# POWER.net
KiCad netlist of a schematic drawn in Altium Designer
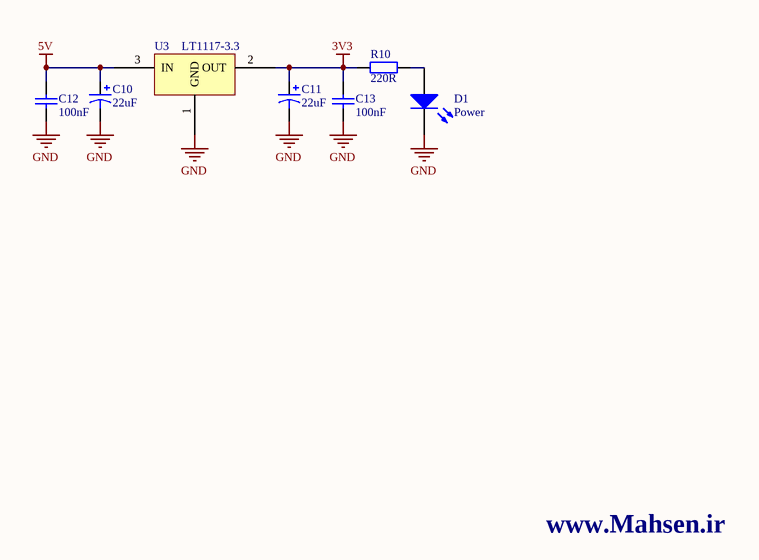
[diagram p0: POWER.SchDoc]

(export (version "E")
  (design (tool "Eeschema 10.0.6"))
  (components
    (comp (ref "C10")
      (value "22uF")
      (footprint "CAPR5-4X5")
      (description "Polarized Capacitor (Surface Mount)")
      (fields (field (name "PUBLISHER") "Altium Limited"))
      (libsource (lib "Miscellaneous Devices") (part "Cap Pol3"))
    )
    (comp (ref "C11")
      (value "22uF")
      (footprint "CAPR5-4X5")
      (description "Polarized Capacitor (Surface Mount)")
      (fields (field (name "PUBLISHER") "Altium Limited"))
      (libsource (lib "Miscellaneous Devices") (part "Cap Pol3"))
    )
    (comp (ref "C12")
      (value "100nF")
      (footprint "0805")
      (description "Capacitor")
      (fields (field (name "PUBLISHER") "Altium Limited"))
      (libsource (lib "Miscellaneous Devices") (part "Cap"))
    )
    (comp (ref "C13")
      (value "100nF")
      (footprint "0805")
      (description "Capacitor")
      (fields (field (name "PUBLISHER") "Altium Limited"))
      (libsource (lib "Miscellaneous Devices") (part "Cap"))
    )
    (comp (ref "D1")
      (value "Power")
      (footprint "3.5X2.8X1.9")
      (description "Typical BLUE SiC LED")
      (fields (field (name "PUBLISHER") "Altium Limited"))
      (libsource (lib "Miscellaneous Devices") (part "LED3"))
    )
    (comp (ref "R10")
      (value "220R")
      (footprint "0805")
      (description "Resistor")
      (fields (field (name "PUBLISHER") "Altium Limited"))
      (libsource (lib "Miscellaneous Devices") (part "Res2"))
    )
    (comp (ref "U3")
      (value "LT1117-3.3")
      (footprint "SOT223_4")
      (libsource (lib "Lotfi") (part "LT1117-3.3"))
    )
  )
  (nets
    (net (code "1") (name "3V3") (class "Default")
      (node (ref "C11") (pin "1") (pinfunction "1_1") (pintype "passive"))
      (node (ref "C13") (pin "1") (pinfunction "1_1") (pintype "passive"))
      (node (ref "R10") (pin "1") (pinfunction "1_1") (pintype "passive"))
      (node (ref "U3") (pin "2") (pinfunction "OUT_2") (pintype "passive"))
    )
    (net (code "2") (name "5V") (class "Default")
      (node (ref "C10") (pin "1") (pinfunction "1_1") (pintype "passive"))
      (node (ref "C12") (pin "1") (pinfunction "1_1") (pintype "passive"))
      (node (ref "U3") (pin "3") (pinfunction "IN_3") (pintype "passive"))
    )
    (net (code "3") (name "GND") (class "Default")
      (node (ref "C10") (pin "2") (pinfunction "2_2") (pintype "passive"))
      (node (ref "C11") (pin "2") (pinfunction "2_2") (pintype "passive"))
      (node (ref "C12") (pin "2") (pinfunction "2_2") (pintype "passive"))
      (node (ref "C13") (pin "2") (pinfunction "2_2") (pintype "passive"))
      (node (ref "D1") (pin "2") (pinfunction "K_2") (pintype "passive"))
      (node (ref "U3") (pin "1") (pinfunction "GND_1") (pintype "passive"))
    )
    (net (code "4") (name "Net-(D1-A)") (class "Default")
      (node (ref "D1") (pin "1") (pinfunction "A_1") (pintype "passive"))
      (node (ref "R10") (pin "2") (pinfunction "2_2") (pintype "passive"))
    )
  )
)
